# Auto_old.net
KiCad netlist of a schematic drawn in Altium Designer
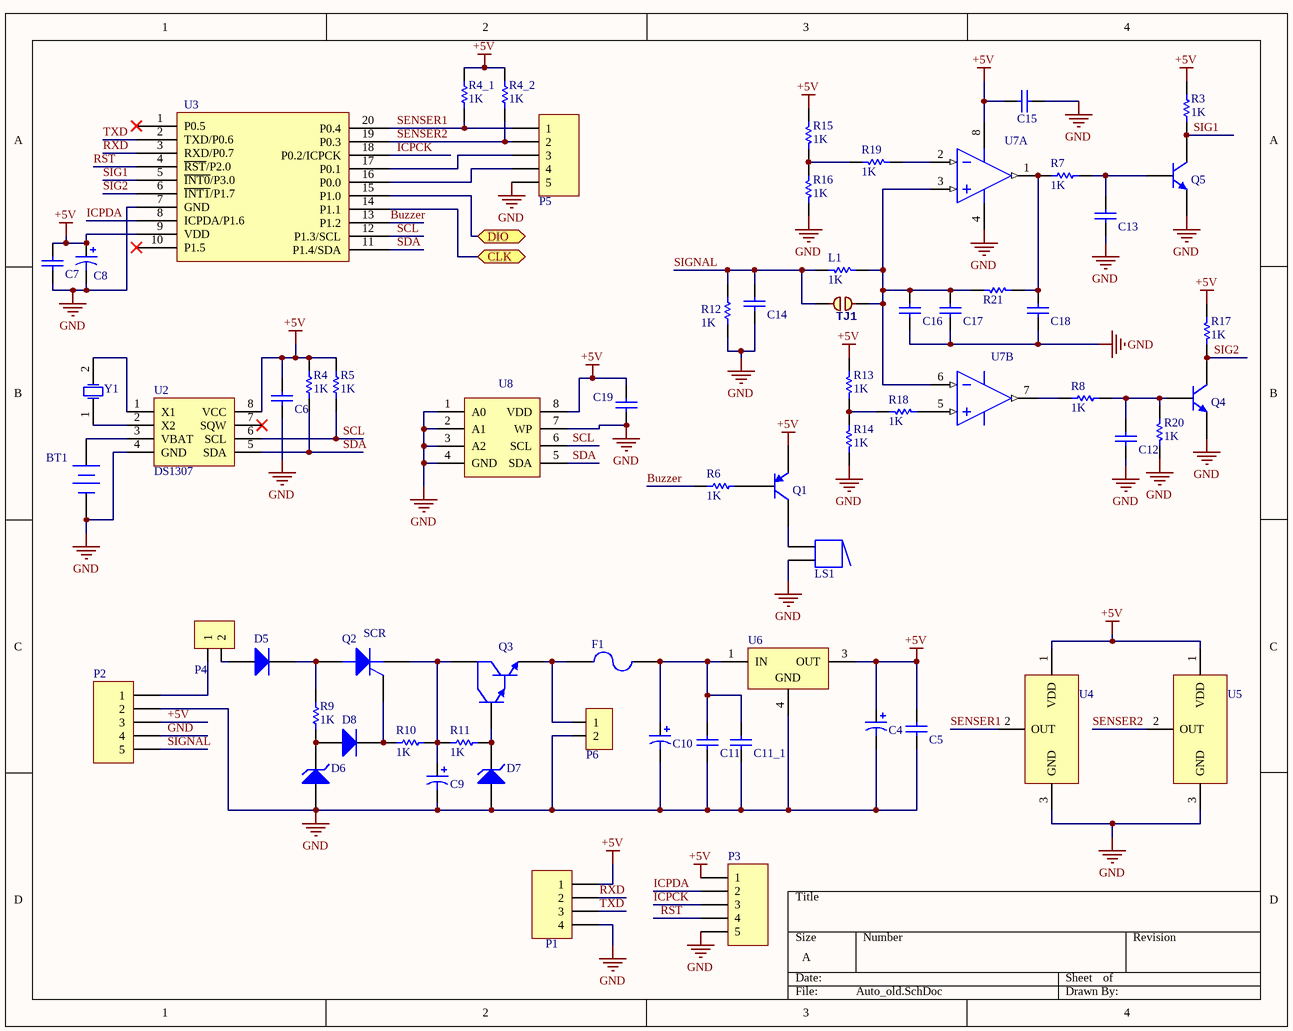
[diagram p0: Auto_old.SchDoc]

(export (version "E")
  (design (tool "Eeschema 10.0.6"))
  (components
    (comp (ref "BT1")
      (value "Battery")
      (footprint "Battery Holder(CR2032)")
      (description "Cell Battery")
      (fields (field (name "PUBLISHER") "Altium Limited"))
      (libsource (lib "Ravi") (part "Battery"))
    )
    (comp (ref "C4")
      (value "Capacitor_Electrolytic")
      (footprint "C1000uF25V")
      (libsource (lib "Ravi") (part "Capacitor_Electrolytic"))
    )
    (comp (ref "C5")
      (value "Capacitor_Ceramic")
      (footprint "C0603")
      (libsource (lib "Devices") (part "Capacitor_Ceramic"))
    )
    (comp (ref "C6")
      (value "Capacitor_Ceramic")
      (footprint "C0603")
      (libsource (lib "Devices") (part "Capacitor_Ceramic"))
    )
    (comp (ref "C7")
      (value "Capacitor_Ceramic")
      (footprint "C0603")
      (libsource (lib "Devices") (part "Capacitor_Ceramic"))
    )
    (comp (ref "C8")
      (value "Capacitor_Electrolytic")
      (footprint "C10uF25V")
      (libsource (lib "Ravi") (part "Capacitor_Electrolytic"))
    )
    (comp (ref "C9")
      (value "Capacitor_Electrolytic")
      (footprint "C1000uF50V")
      (libsource (lib "Ravi") (part "Capacitor_Electrolytic"))
    )
    (comp (ref "C10")
      (value "Capacitor_Electrolytic")
      (footprint "C1000uF50V")
      (libsource (lib "Ravi") (part "Capacitor_Electrolytic"))
    )
    (comp (ref "C11")
      (value "Capacitor_Ceramic")
      (footprint "C0805")
      (libsource (lib "Devices") (part "Capacitor_Ceramic"))
    )
    (comp (ref "C11_1")
      (value "Capacitor_Ceramic")
      (footprint "Capacitor_Ceramic")
      (libsource (lib "Devices") (part "Capacitor_Ceramic"))
    )
    (comp (ref "C12")
      (value "Capacitor_Ceramic")
      (footprint "C0603")
      (libsource (lib "Devices") (part "Capacitor_Ceramic"))
    )
    (comp (ref "C13")
      (value "Capacitor_Ceramic")
      (footprint "C0603")
      (libsource (lib "Devices") (part "Capacitor_Ceramic"))
    )
    (comp (ref "C14")
      (value "Capacitor_Ceramic")
      (footprint "C0603")
      (libsource (lib "Devices") (part "Capacitor_Ceramic"))
    )
    (comp (ref "C15")
      (value "Capacitor_Ceramic")
      (footprint "C0603")
      (libsource (lib "Devices") (part "Capacitor_Ceramic"))
    )
    (comp (ref "C16")
      (value "Capacitor_Ceramic")
      (footprint "C0603")
      (libsource (lib "Devices") (part "Capacitor_Ceramic"))
    )
    (comp (ref "C17")
      (value "Capacitor_Ceramic")
      (footprint "C0603")
      (libsource (lib "Devices") (part "Capacitor_Ceramic"))
    )
    (comp (ref "C18")
      (value "Capacitor_Ceramic")
      (footprint "C0603")
      (libsource (lib "Devices") (part "Capacitor_Ceramic"))
    )
    (comp (ref "C19")
      (value "Capacitor_Ceramic")
      (footprint "C0603")
      (libsource (lib "Devices") (part "Capacitor_Ceramic"))
    )
    (comp (ref "D5") (value "Diode") (footprint "DO-241") (libsource (lib "Ravi") (part "Diode")))
    (comp (ref "D6")
      (value "D Zener")
      (footprint "LL-41")
      (description "Zener Diode")
      (fields (field (name "PUBLISHER") "Altium Limited"))
      (libsource (lib "Ravi") (part "D Zener"))
    )
    (comp (ref "D7")
      (value "D Zener")
      (footprint "LL-41")
      (description "Zener Diode")
      (fields (field (name "PUBLISHER") "Altium Limited"))
      (libsource (lib "Ravi") (part "D Zener"))
    )
    (comp (ref "D8") (value "Diode") (footprint "DO-241") (libsource (lib "Ravi") (part "Diode")))
    (comp (ref "F1") (value "Fuse") (footprint "1812(PTC Fuse)") (libsource (lib "Devices") (part "Fuse")))
    (comp (ref "L1")
      (value "1K")
      (footprint "Axial 1/4W")
      (description "Resistor")
      (fields (field (name "Comment") "Res1") (field (name "PUBLISHER") "Altium Limited"))
      (libsource (lib "Devices") (part "Res1"))
    )
    (comp (ref "LS1")
      (value "Buzzer")
      (footprint "Buzzer")
      (description "Magnetic Transducer Buzzer")
      (fields (field (name "PUBLISHER") "Altium Limited"))
      (libsource (lib "Ravi") (part "Buzzer"))
    )
    (comp (ref "P1")
      (value "Header 4")
      (footprint "HDR1X4")
      (description "Header, 4-Pin")
      (fields (field (name "PUBLISHER") "Altium Limited"))
      (libsource (lib "Ravi") (part "Header 4"))
    )
    (comp (ref "P2")
      (value "Header 5")
      (footprint "Connector_508_5pin")
      (description "Header, 5-Pin")
      (fields (field (name "PUBLISHER") "Altium Limited"))
      (libsource (lib "Connector") (part "Header 5"))
    )
    (comp (ref "P3")
      (value "Header 5")
      (footprint "HDR1X5")
      (description "Header, 5-Pin")
      (fields (field (name "PUBLISHER") "Altium Limited"))
      (libsource (lib "Ravi") (part "Header 5"))
    )
    (comp (ref "P4")
      (value "Header 2X1")
      (footprint "HDR1X2_2515")
      (libsource (lib "Connector") (part "Header 2X1"))
    )
    (comp (ref "P5")
      (value "Header 5")
      (footprint "HDR1X5_2515")
      (description "Header, 5-Pin")
      (fields (field (name "PUBLISHER") "Altium Limited"))
      (libsource (lib "Ravi") (part "Header 5"))
    )
    (comp (ref "P6")
      (value "Header 2X1")
      (footprint "HDR1X2_2515")
      (libsource (lib "") (part "Header 2X1_1"))
    )
    (comp (ref "Q1") (value "PNP") (footprint "SOT-23") (libsource (lib "Ravi") (part "PNP")))
    (comp (ref "Q2")
      (value "SCR")
      (footprint "DPAK_SOT423_252")
      (description "Silicon Controlled Rectifier")
      (fields (field (name "PUBLISHER") "Altium Limited"))
      (libsource (lib "Devices") (part "SCR"))
    )
    (comp (ref "Q3")
      (value "NPN1")
      (footprint "DPAK_SOT423_252")
      (description "NPN Darlington Bipolar Transistor")
      (fields (field (name "PUBLISHER") "Altium Limited"))
      (libsource (lib "Devices") (part "NPN1"))
    )
    (comp (ref "Q4") (value "NPN") (footprint "SOT-23") (libsource (lib "Ravi") (part "NPN")))
    (comp (ref "Q5") (value "NPN") (footprint "SOT-23") (libsource (lib "Ravi") (part "NPN")))
    (comp (ref "R3")
      (value "1K")
      (footprint "R0603")
      (description "Resistor")
      (fields (field (name "Comment") "Res1") (field (name "PUBLISHER") "Altium Limited"))
      (libsource (lib "Devices") (part "Res1"))
    )
    (comp (ref "R4")
      (value "1K")
      (footprint "R0603")
      (description "Resistor")
      (fields (field (name "Comment") "Res1") (field (name "PUBLISHER") "Altium Limited"))
      (libsource (lib "Devices") (part "Res1"))
    )
    (comp (ref "R4_1")
      (value "1K")
      (footprint "R0603")
      (description "Resistor")
      (fields (field (name "Comment") "Res1") (field (name "PUBLISHER") "Altium Limited"))
      (libsource (lib "Devices") (part "Res1"))
    )
    (comp (ref "R4_2")
      (value "1K")
      (footprint "R0603")
      (description "Resistor")
      (fields (field (name "Comment") "Res1") (field (name "PUBLISHER") "Altium Limited"))
      (libsource (lib "Devices") (part "Res1"))
    )
    (comp (ref "R5")
      (value "1K")
      (footprint "R0603")
      (description "Resistor")
      (fields (field (name "Comment") "Res1") (field (name "PUBLISHER") "Altium Limited"))
      (libsource (lib "Devices") (part "Res1"))
    )
    (comp (ref "R6")
      (value "1K")
      (footprint "R0603")
      (description "Resistor")
      (fields (field (name "Comment") "Res1") (field (name "PUBLISHER") "Altium Limited"))
      (libsource (lib "Devices") (part "Res1"))
    )
    (comp (ref "R7")
      (value "1K")
      (footprint "R0603")
      (description "Resistor")
      (fields (field (name "Comment") "Res1") (field (name "PUBLISHER") "Altium Limited"))
      (libsource (lib "Devices") (part "Res1"))
    )
    (comp (ref "R8")
      (value "1K")
      (footprint "R0603")
      (description "Resistor")
      (fields (field (name "Comment") "Res1") (field (name "PUBLISHER") "Altium Limited"))
      (libsource (lib "Devices") (part "Res1"))
    )
    (comp (ref "R9")
      (value "1K")
      (footprint "R1206")
      (description "Resistor")
      (fields (field (name "Comment") "Res1") (field (name "PUBLISHER") "Altium Limited"))
      (libsource (lib "Devices") (part "Res1"))
    )
    (comp (ref "R10")
      (value "1K")
      (footprint "R1206")
      (description "Resistor")
      (fields (field (name "Comment") "Res1") (field (name "PUBLISHER") "Altium Limited"))
      (libsource (lib "Devices") (part "Res1"))
    )
    (comp (ref "R11")
      (value "1K")
      (footprint "R1206")
      (description "Resistor")
      (fields (field (name "Comment") "Res1") (field (name "PUBLISHER") "Altium Limited"))
      (libsource (lib "Devices") (part "Res1"))
    )
    (comp (ref "R12")
      (value "1K")
      (footprint "R0603")
      (description "Resistor")
      (fields (field (name "Comment") "Res1") (field (name "PUBLISHER") "Altium Limited"))
      (libsource (lib "Devices") (part "Res1"))
    )
    (comp (ref "R13")
      (value "1K")
      (footprint "R0603")
      (description "Resistor")
      (fields (field (name "Comment") "Res1") (field (name "PUBLISHER") "Altium Limited"))
      (libsource (lib "Devices") (part "Res1"))
    )
    (comp (ref "R14")
      (value "1K")
      (footprint "R0603")
      (description "Resistor")
      (fields (field (name "Comment") "Res1") (field (name "PUBLISHER") "Altium Limited"))
      (libsource (lib "Devices") (part "Res1"))
    )
    (comp (ref "R15")
      (value "1K")
      (footprint "R0603")
      (description "Resistor")
      (fields (field (name "Comment") "Res1") (field (name "PUBLISHER") "Altium Limited"))
      (libsource (lib "Devices") (part "Res1"))
    )
    (comp (ref "R16")
      (value "1K")
      (footprint "R0603")
      (description "Resistor")
      (fields (field (name "Comment") "Res1") (field (name "PUBLISHER") "Altium Limited"))
      (libsource (lib "Devices") (part "Res1"))
    )
    (comp (ref "R17")
      (value "1K")
      (footprint "R0603")
      (description "Resistor")
      (fields (field (name "Comment") "Res1") (field (name "PUBLISHER") "Altium Limited"))
      (libsource (lib "Devices") (part "Res1"))
    )
    (comp (ref "R18")
      (value "1K")
      (footprint "R0603")
      (description "Resistor")
      (fields (field (name "Comment") "Res1") (field (name "PUBLISHER") "Altium Limited"))
      (libsource (lib "Devices") (part "Res1"))
    )
    (comp (ref "R19")
      (value "1K")
      (footprint "R0603")
      (description "Resistor")
      (fields (field (name "Comment") "Res1") (field (name "PUBLISHER") "Altium Limited"))
      (libsource (lib "Devices") (part "Res1"))
    )
    (comp (ref "R20")
      (value "1K")
      (footprint "R0603")
      (description "Resistor")
      (fields (field (name "Comment") "Res1") (field (name "PUBLISHER") "Altium Limited"))
      (libsource (lib "Devices") (part "Res1"))
    )
    (comp (ref "R21")
      (value "Res1")
      (footprint "R0603")
      (description "Resistor")
      (fields (field (name "PUBLISHER") "Altium Limited"))
      (libsource (lib "Devices") (part "Res1"))
    )
    (comp (ref "TJ1")
      (value "JUMPER-PAD-2-NO_BY_TRACE")
      (footprint "PAD_JUMPER_2_NO")
      (libsource (lib "Ravi") (part "JUMPER-PAD-2-NO_BY_TRACE"))
    )
    (comp (ref "U2") (value "DS1307") (footprint "SOIC-8N") (libsource (lib "Ravi") (part "DS1307")))
    (comp (ref "U3") (value "8051") (footprint "TSSOP-20") (libsource (lib "Ravi") (part "N76E003")))
    (comp (ref "U4")
      (value "Hall effect Switch")
      (footprint "SOT-23")
      (libsource (lib "Devices") (part "AH1802"))
    )
    (comp (ref "U5")
      (value "Hall effect Switch")
      (footprint "SOT-23")
      (libsource (lib "Devices") (part "AH1802"))
    )
    (comp (ref "U6")
      (value "LM7805_DPAK")
      (footprint "DPAK_SOT423_252")
      (libsource (lib "Ravi") (part "LM7805_DPAK"))
    )
    (comp (ref "U7") (value "OP-AMP") (footprint "SOIC-8N") (libsource (lib "Ravi") (part "LM158")))
    (comp (ref "U8") (value "EEPROM") (footprint "SOIC-8N") (libsource (lib "Ravi") (part "24Cxx")))
    (comp (ref "Y1")
      (value "XTAL")
      (footprint "Craystal")
      (description "Crystal Oscillator")
      (fields (field (name "PUBLISHER") "Altium Limited"))
      (libsource (lib "Ravi") (part "XTAL"))
    )
  )
  (nets
    (net (code "1") (name "+5V") (class "Default")
      (node (ref "C15") (pin "2") (pinfunction "2_2") (pintype "passive"))
      (node (ref "C19") (pin "1") (pinfunction "1_1") (pintype "passive"))
      (node (ref "C4") (pin "1") (pinfunction "1_1") (pintype "passive"))
      (node (ref "C5") (pin "2") (pinfunction "2_2") (pintype "passive"))
      (node (ref "C6") (pin "2") (pinfunction "2_2") (pintype "passive"))
      (node (ref "C7") (pin "2") (pinfunction "2_2") (pintype "passive"))
      (node (ref "C8") (pin "1") (pinfunction "1_1") (pintype "passive"))
      (node (ref "P1") (pin "1") (pinfunction "1_1") (pintype "passive"))
      (node (ref "P2") (pin "3") (pinfunction "3_3") (pintype "passive"))
      (node (ref "P3") (pin "1") (pinfunction "1_1") (pintype "passive"))
      (node (ref "Q1") (pin "2") (pinfunction "E_2") (pintype "passive"))
      (node (ref "R13") (pin "1") (pinfunction "1_1") (pintype "passive"))
      (node (ref "R15") (pin "2") (pinfunction "2_2") (pintype "passive"))
      (node (ref "R17") (pin "2") (pinfunction "2_2") (pintype "passive"))
      (node (ref "R3") (pin "1") (pinfunction "1_1") (pintype "passive"))
      (node (ref "R4") (pin "2") (pinfunction "2_2") (pintype "passive"))
      (node (ref "R4_1") (pin "2") (pinfunction "2_2") (pintype "passive"))
      (node (ref "R4_2") (pin "2") (pinfunction "2_2") (pintype "passive"))
      (node (ref "R5") (pin "2") (pinfunction "2_2") (pintype "passive"))
      (node (ref "U2") (pin "8") (pinfunction "VCC_8") (pintype "power_in"))
      (node (ref "U3") (pin "9") (pinfunction "VDD_9") (pintype "power_in"))
      (node (ref "U4") (pin "1") (pinfunction "VDD_1") (pintype "passive"))
      (node (ref "U5") (pin "1") (pinfunction "VDD_1") (pintype "passive"))
      (node (ref "U6") (pin "3") (pinfunction "OUT_3") (pintype "power_in"))
      (node (ref "U7") (pin "8") (pinfunction "VCC_8") (pintype "power_in"))
      (node (ref "U8") (pin "8") (pinfunction "VDD_8") (pintype "power_in"))
    )
    (net (code "2") (name "/Buzzer") (class "Default")
      (node (ref "R6") (pin "2") (pinfunction "2_2") (pintype "passive"))
      (node (ref "U3") (pin "13") (pinfunction "P1.2_13") (pintype "passive"))
    )
    (net (code "3") (name "/CLK") (class "Default")
      (node (ref "U3") (pin "14") (pinfunction "P1.1_14") (pintype "passive"))
    )
    (net (code "4") (name "/DIO") (class "Default")
      (node (ref "U3") (pin "15") (pinfunction "P1.0_15") (pintype "passive"))
    )
    (net (code "5") (name "/ICPCK") (class "Default")
      (node (ref "P3") (pin "3") (pinfunction "3_3") (pintype "passive"))
      (node (ref "U3") (pin "18") (pinfunction "P0.2/ICPCK_18") (pintype "passive"))
    )
    (net (code "6") (name "/ICPDA") (class "Default")
      (node (ref "P3") (pin "2") (pinfunction "2_2") (pintype "passive"))
      (node (ref "U3") (pin "8") (pinfunction "ICPDA/P1.6_8") (pintype "passive"))
    )
    (net (code "7") (name "/RST") (class "Default")
      (node (ref "P3") (pin "4") (pinfunction "4_4") (pintype "passive"))
      (node (ref "U3") (pin "4") (pinfunction "~{RST}/P2.0_4") (pintype "passive"))
    )
    (net (code "8") (name "/RXD") (class "Default")
      (node (ref "P1") (pin "2") (pinfunction "2_2") (pintype "passive"))
      (node (ref "U3") (pin "3") (pinfunction "RXD/P0.7_3") (pintype "passive"))
    )
    (net (code "9") (name "/SCL") (class "Default")
      (node (ref "R5") (pin "1") (pinfunction "1_1") (pintype "passive"))
      (node (ref "U2") (pin "6") (pinfunction "SCL_6") (pintype "passive"))
      (node (ref "U3") (pin "12") (pinfunction "P1.3/SCL_12") (pintype "passive"))
      (node (ref "U8") (pin "6") (pinfunction "SCL_6") (pintype "passive"))
    )
    (net (code "10") (name "/SDA") (class "Default")
      (node (ref "R4") (pin "1") (pinfunction "1_1") (pintype "passive"))
      (node (ref "U2") (pin "5") (pinfunction "SDA_5") (pintype "passive"))
      (node (ref "U3") (pin "11") (pinfunction "P1.4/SDA_11") (pintype "passive"))
      (node (ref "U8") (pin "5") (pinfunction "SDA_5") (pintype "passive"))
    )
    (net (code "11") (name "/SENSER1") (class "Default")
      (node (ref "P5") (pin "1") (pinfunction "1_1") (pintype "passive"))
      (node (ref "R4_1") (pin "1") (pinfunction "1_1") (pintype "passive"))
      (node (ref "U3") (pin "20") (pinfunction "P0.4_20") (pintype "passive"))
      (node (ref "U4") (pin "2") (pinfunction "OUT_2") (pintype "passive"))
    )
    (net (code "12") (name "/SENSER2") (class "Default")
      (node (ref "P5") (pin "2") (pinfunction "2_2") (pintype "passive"))
      (node (ref "R4_2") (pin "1") (pinfunction "1_1") (pintype "passive"))
      (node (ref "U3") (pin "19") (pinfunction "P0.3_19") (pintype "passive"))
      (node (ref "U5") (pin "2") (pinfunction "OUT_2") (pintype "passive"))
    )
    (net (code "13") (name "/SIG1") (class "Default")
      (node (ref "Q5") (pin "3") (pinfunction "C_3") (pintype "passive"))
      (node (ref "R3") (pin "2") (pinfunction "2_2") (pintype "passive"))
      (node (ref "U3") (pin "5") (pinfunction "~{INT0}/P3.0_5") (pintype "passive"))
    )
    (net (code "14") (name "/SIG2") (class "Default")
      (node (ref "Q4") (pin "3") (pinfunction "C_3") (pintype "passive"))
      (node (ref "R17") (pin "1") (pinfunction "1_1") (pintype "passive"))
      (node (ref "U3") (pin "6") (pinfunction "~{INT1}/P1.7_6") (pintype "passive"))
    )
    (net (code "15") (name "/SIGNAL") (class "Default")
      (node (ref "C14") (pin "2") (pinfunction "2_2") (pintype "passive"))
      (node (ref "L1") (pin "1") (pinfunction "1_1") (pintype "passive"))
      (node (ref "P2") (pin "5") (pinfunction "5_5") (pintype "passive"))
      (node (ref "R12") (pin "1") (pinfunction "1_1") (pintype "passive"))
      (node (ref "TJ1") (pin "1") (pinfunction "1_1") (pintype "passive"))
    )
    (net (code "16") (name "/TXD") (class "Default")
      (node (ref "P1") (pin "3") (pinfunction "3_3") (pintype "passive"))
      (node (ref "U3") (pin "2") (pinfunction "TXD/P0.6_2") (pintype "passive"))
    )
    (net (code "17") (name "GND") (class "Default")
      (node (ref "BT1") (pin "2") (pinfunction "-_2") (pintype "passive"))
      (node (ref "C10") (pin "2") (pinfunction "2_2") (pintype "passive"))
      (node (ref "C11") (pin "1") (pinfunction "1_1") (pintype "passive"))
      (node (ref "C11_1") (pin "1") (pinfunction "1_1") (pintype "passive"))
      (node (ref "C12") (pin "1") (pinfunction "1_1") (pintype "passive"))
      (node (ref "C13") (pin "1") (pinfunction "1_1") (pintype "passive"))
      (node (ref "C14") (pin "1") (pinfunction "1_1") (pintype "passive"))
      (node (ref "C15") (pin "1") (pinfunction "1_1") (pintype "passive"))
      (node (ref "C16") (pin "2") (pinfunction "2_2") (pintype "passive"))
      (node (ref "C17") (pin "2") (pinfunction "2_2") (pintype "passive"))
      (node (ref "C18") (pin "2") (pinfunction "2_2") (pintype "passive"))
      (node (ref "C19") (pin "2") (pinfunction "2_2") (pintype "passive"))
      (node (ref "C4") (pin "2") (pinfunction "2_2") (pintype "passive"))
      (node (ref "C5") (pin "1") (pinfunction "1_1") (pintype "passive"))
      (node (ref "C6") (pin "1") (pinfunction "1_1") (pintype "passive"))
      (node (ref "C7") (pin "1") (pinfunction "1_1") (pintype "passive"))
      (node (ref "C8") (pin "2") (pinfunction "2_2") (pintype "passive"))
      (node (ref "C9") (pin "2") (pinfunction "2_2") (pintype "passive"))
      (node (ref "D6") (pin "1") (pinfunction "A_1") (pintype "passive"))
      (node (ref "D7") (pin "1") (pinfunction "A_1") (pintype "passive"))
      (node (ref "LS1") (pin "2") (pinfunction "2_2") (pintype "passive"))
      (node (ref "P1") (pin "4") (pinfunction "4_4") (pintype "passive"))
      (node (ref "P2") (pin "2") (pinfunction "2_2") (pintype "passive"))
      (node (ref "P2") (pin "4") (pinfunction "4_4") (pintype "passive"))
      (node (ref "P3") (pin "5") (pinfunction "5_5") (pintype "passive"))
      (node (ref "P5") (pin "5") (pinfunction "5_5") (pintype "passive"))
      (node (ref "P6") (pin "2") (pinfunction "2_2") (pintype "passive"))
      (node (ref "Q4") (pin "2") (pinfunction "E_2") (pintype "passive"))
      (node (ref "Q5") (pin "2") (pinfunction "E_2") (pintype "passive"))
      (node (ref "R12") (pin "2") (pinfunction "2_2") (pintype "passive"))
      (node (ref "R14") (pin "1") (pinfunction "1_1") (pintype "passive"))
      (node (ref "R16") (pin "1") (pinfunction "1_1") (pintype "passive"))
      (node (ref "R20") (pin "2") (pinfunction "2_2") (pintype "passive"))
      (node (ref "U2") (pin "4") (pinfunction "GND_4") (pintype "power_in"))
      (node (ref "U3") (pin "7") (pinfunction "GND_7") (pintype "power_in"))
      (node (ref "U4") (pin "3") (pinfunction "GND_3") (pintype "passive"))
      (node (ref "U5") (pin "3") (pinfunction "GND_3") (pintype "passive"))
      (node (ref "U6") (pin "4") (pinfunction "GND_4") (pintype "power_in"))
      (node (ref "U7") (pin "4") (pinfunction "GND_4") (pintype "power_in"))
      (node (ref "U8") (pin "1") (pinfunction "A0_1") (pintype "passive"))
      (node (ref "U8") (pin "2") (pinfunction "A1_2") (pintype "passive"))
      (node (ref "U8") (pin "3") (pinfunction "A2_3") (pintype "passive"))
      (node (ref "U8") (pin "4") (pinfunction "GND_4") (pintype "power_in"))
      (node (ref "U8") (pin "7") (pinfunction "WP_7") (pintype "passive"))
    )
    (net (code "18") (name "Net-(BT1-+)") (class "Default")
      (node (ref "BT1") (pin "1") (pinfunction "+_1") (pintype "passive"))
      (node (ref "U2") (pin "3") (pinfunction "VBAT_3") (pintype "passive"))
    )
    (net (code "19") (name "Net-(D5-A)") (class "Default")
      (node (ref "D5") (pin "1") (pinfunction "A_1") (pintype "passive"))
      (node (ref "P4") (pin "2") (pinfunction "2_2") (pintype "passive"))
    )
    (net (code "20") (name "Net-(D5-K)") (class "Default")
      (node (ref "D5") (pin "2") (pinfunction "K_2") (pintype "passive"))
      (node (ref "Q2") (pin "4") (pinfunction "A_4") (pintype "passive"))
      (node (ref "R9") (pin "2") (pinfunction "2_2") (pintype "passive"))
    )
    (net (code "21") (name "Net-(D6-K)") (class "Default")
      (node (ref "D6") (pin "2") (pinfunction "K_2") (pintype "passive"))
      (node (ref "D8") (pin "1") (pinfunction "A_1") (pintype "passive"))
      (node (ref "R9") (pin "1") (pinfunction "1_1") (pintype "passive"))
    )
    (net (code "22") (name "Net-(D7-K)") (class "Default")
      (node (ref "D7") (pin "2") (pinfunction "K_2") (pintype "passive"))
      (node (ref "Q3") (pin "1") (pinfunction "B_1") (pintype "passive"))
      (node (ref "R11") (pin "1") (pinfunction "1_1") (pintype "passive"))
    )
    (net (code "23") (name "Net-(D8-K)") (class "Default")
      (node (ref "D8") (pin "2") (pinfunction "K_2") (pintype "passive"))
      (node (ref "Q2") (pin "3") (pinfunction "G_3") (pintype "passive"))
      (node (ref "R10") (pin "2") (pinfunction "2_2") (pintype "passive"))
    )
    (net (code "24") (name "Net-(P2-Pad1)") (class "Default")
      (node (ref "P2") (pin "1") (pinfunction "1_1") (pintype "passive"))
      (node (ref "P4") (pin "1") (pinfunction "1_1") (pintype "passive"))
    )
    (net (code "25") (name "Net-(Q1-B)") (class "Default")
      (node (ref "Q1") (pin "1") (pinfunction "B_1") (pintype "passive"))
      (node (ref "R6") (pin "1") (pinfunction "1_1") (pintype "passive"))
    )
    (net (code "26") (name "Net-(Q1-C)") (class "Default")
      (node (ref "LS1") (pin "1") (pinfunction "1_1") (pintype "passive"))
      (node (ref "Q1") (pin "3") (pinfunction "C_3") (pintype "passive"))
    )
    (net (code "27") (name "Net-(Q2-K)") (class "Default")
      (node (ref "C9") (pin "1") (pinfunction "1_1") (pintype "passive"))
      (node (ref "Q2") (pin "1") (pinfunction "K_1") (pintype "passive"))
      (node (ref "Q3") (pin "4") (pinfunction "C_4") (pintype "passive"))
      (node (ref "R10") (pin "1") (pinfunction "1_1") (pintype "passive"))
      (node (ref "R11") (pin "2") (pinfunction "2_2") (pintype "passive"))
    )
    (net (code "28") (name "Net-(Q3-E)") (class "Default")
      (node (ref "F1") (pin "1") (pinfunction "1_1") (pintype "passive"))
      (node (ref "P6") (pin "1") (pinfunction "1_1") (pintype "passive"))
      (node (ref "Q3") (pin "3") (pinfunction "E_3") (pintype "passive"))
    )
    (net (code "29") (name "Net-(Q4-B)") (class "Default")
      (node (ref "C12") (pin "2") (pinfunction "2_2") (pintype "passive"))
      (node (ref "Q4") (pin "1") (pinfunction "B_1") (pintype "passive"))
      (node (ref "R20") (pin "1") (pinfunction "1_1") (pintype "passive"))
      (node (ref "R8") (pin "2") (pinfunction "2_2") (pintype "passive"))
    )
    (net (code "30") (name "Net-(Q5-B)") (class "Default")
      (node (ref "C13") (pin "2") (pinfunction "2_2") (pintype "passive"))
      (node (ref "Q5") (pin "1") (pinfunction "B_1") (pintype "passive"))
      (node (ref "R7") (pin "2") (pinfunction "2_2") (pintype "passive"))
    )
    (net (code "31") (name "Net-(R13-Pad2)") (class "Default")
      (node (ref "R13") (pin "2") (pinfunction "2_2") (pintype "passive"))
      (node (ref "R14") (pin "2") (pinfunction "2_2") (pintype "passive"))
      (node (ref "R18") (pin "2") (pinfunction "2_2") (pintype "passive"))
    )
    (net (code "32") (name "Net-(R15-Pad1)") (class "Default")
      (node (ref "R15") (pin "1") (pinfunction "1_1") (pintype "passive"))
      (node (ref "R16") (pin "2") (pinfunction "2_2") (pintype "passive"))
      (node (ref "R19") (pin "2") (pinfunction "2_2") (pintype "passive"))
    )
    (net (code "33") (name "Net-(U2-X1)") (class "Default")
      (node (ref "U2") (pin "1") (pinfunction "X1_1") (pintype "passive"))
      (node (ref "Y1") (pin "2") (pinfunction "OSC2_2") (pintype "passive"))
    )
    (net (code "34") (name "Net-(U2-X2)") (class "Default")
      (node (ref "U2") (pin "2") (pinfunction "X2_2") (pintype "passive"))
      (node (ref "Y1") (pin "1") (pinfunction "OSC1_1") (pintype "passive"))
    )
    (net (code "35") (name "Net-(U3-P0.0)") (class "Default")
      (node (ref "P5") (pin "4") (pinfunction "4_4") (pintype "passive"))
      (node (ref "U3") (pin "16") (pinfunction "P0.0_16") (pintype "passive"))
    )
    (net (code "36") (name "Net-(U3-P0.1)") (class "Default")
      (node (ref "P5") (pin "3") (pinfunction "3_3") (pintype "passive"))
      (node (ref "U3") (pin "17") (pinfunction "P0.1_17") (pintype "passive"))
    )
    (net (code "37") (name "Net-(U6-IN)") (class "Default")
      (node (ref "C10") (pin "1") (pinfunction "1_1") (pintype "passive"))
      (node (ref "C11") (pin "2") (pinfunction "2_2") (pintype "passive"))
      (node (ref "C11_1") (pin "2") (pinfunction "2_2") (pintype "passive"))
      (node (ref "F1") (pin "2") (pinfunction "2_2") (pintype "passive"))
      (node (ref "U6") (pin "1") (pinfunction "IN_1") (pintype "power_in"))
    )
    (net (code "38") (name "Net-(U7A-IN+)") (class "Default")
      (node (ref "C16") (pin "1") (pinfunction "1_1") (pintype "passive"))
      (node (ref "C17") (pin "1") (pinfunction "1_1") (pintype "passive"))
      (node (ref "L1") (pin "2") (pinfunction "2_2") (pintype "passive"))
      (node (ref "R21") (pin "1") (pinfunction "1_1") (pintype "passive"))
      (node (ref "TJ1") (pin "2") (pinfunction "2_2") (pintype "passive"))
      (node (ref "U7") (pin "3") (pinfunction "IN+_3") (pintype "input"))
      (node (ref "U7") (pin "6") (pinfunction "IN-_6") (pintype "input"))
    )
    (net (code "39") (name "Net-(U7A-IN-)") (class "Default")
      (node (ref "R19") (pin "1") (pinfunction "1_1") (pintype "passive"))
      (node (ref "U7") (pin "2") (pinfunction "IN-_2") (pintype "input"))
    )
    (net (code "40") (name "Net-(U7A-OUT)") (class "Default")
      (node (ref "C18") (pin "1") (pinfunction "1_1") (pintype "passive"))
      (node (ref "R21") (pin "2") (pinfunction "2_2") (pintype "passive"))
      (node (ref "R7") (pin "1") (pinfunction "1_1") (pintype "passive"))
      (node (ref "U7") (pin "1") (pinfunction "OUT_1") (pintype "output"))
    )
    (net (code "41") (name "Net-(U7B-IN+)") (class "Default")
      (node (ref "R18") (pin "1") (pinfunction "1_1") (pintype "passive"))
      (node (ref "U7") (pin "5") (pinfunction "IN+_5") (pintype "input"))
    )
    (net (code "42") (name "Net-(U7B-OUT)") (class "Default")
      (node (ref "R8") (pin "1") (pinfunction "1_1") (pintype "passive"))
      (node (ref "U7") (pin "7") (pinfunction "OUT_7") (pintype "output"))
    )
    (net (code "43") (name "unconnected-(U2-SQW-Pad7)") (class "Default")
      (node (ref "U2") (pin "7") (pinfunction "SQW_7") (pintype "passive+no_connect"))
    )
    (net (code "44") (name "unconnected-(U3-P0.5-Pad1)") (class "Default")
      (node (ref "U3") (pin "1") (pinfunction "P0.5_1") (pintype "passive+no_connect"))
    )
    (net (code "45") (name "unconnected-(U3-P1.5-Pad10)") (class "Default")
      (node (ref "U3") (pin "10") (pinfunction "P1.5_10") (pintype "passive+no_connect"))
    )
  )
)
